# 05_-_I2C.net
KiCad netlist of a schematic drawn in Altium Designer
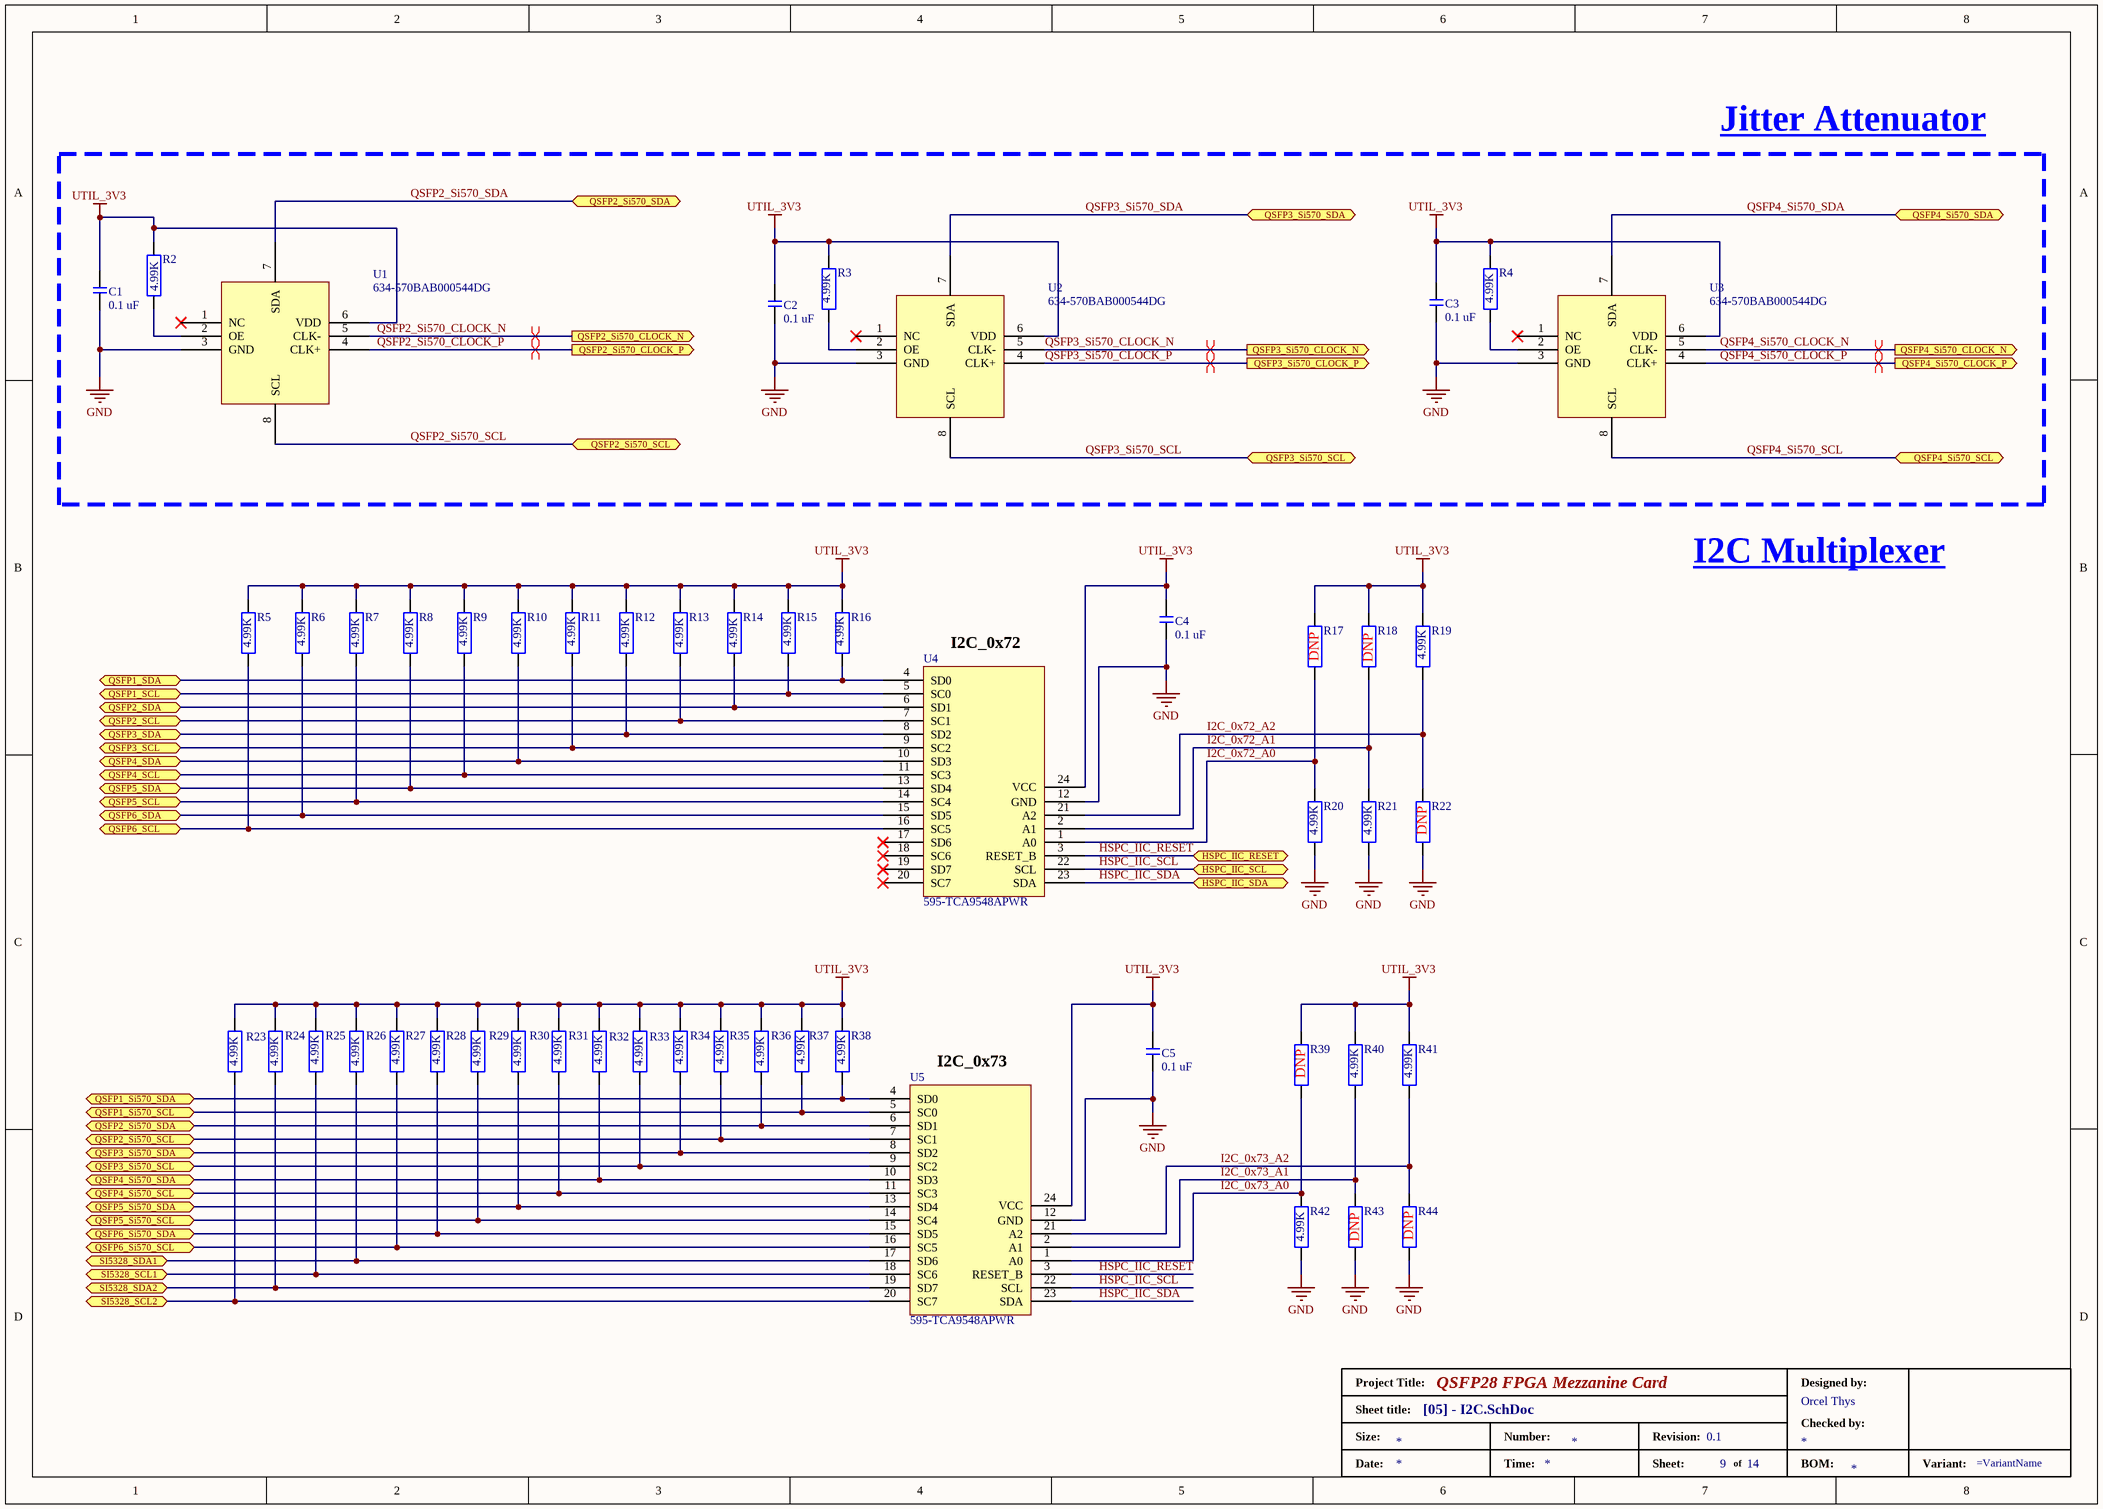
[diagram p0: [05] - I2C.SchDoc]

(export (version "E")
  (design (tool "Eeschema 10.0.6"))
  (components
    (comp (ref "C1")
      (value "0.1 uF")
      (footprint "C0402")
      (description "Cap 0402 0.1 uF 50 V ±10 % Tolerance X7R Surface Mount Multilayer Ceramic Capacitor")
      (fields
        (field (name "MANUFACTURER") "Taiyo Yuden")
        (field (name "MANUFACTURER PART NUMBER") "UMK105B7104KV-FR")
      )
      (libsource (lib "QSFP28_FMC_lib") (part "UMK105B7104KV-FR"))
    )
    (comp (ref "C2")
      (value "0.1 uF")
      (footprint "C0402")
      (description "Cap 0402 0.1 uF 50 V ±10 % Tolerance X7R Surface Mount Multilayer Ceramic Capacitor")
      (fields
        (field (name "MANUFACTURER") "Taiyo Yuden")
        (field (name "MANUFACTURER PART NUMBER") "UMK105B7104KV-FR")
      )
      (libsource (lib "QSFP28_FMC_lib") (part "UMK105B7104KV-FR"))
    )
    (comp (ref "C3")
      (value "0.1 uF")
      (footprint "C0402")
      (description "Cap 0402 0.1 uF 50 V ±10 % Tolerance X7R Surface Mount Multilayer Ceramic Capacitor")
      (fields
        (field (name "MANUFACTURER") "Taiyo Yuden")
        (field (name "MANUFACTURER PART NUMBER") "UMK105B7104KV-FR")
      )
      (libsource (lib "QSFP28_FMC_lib") (part "UMK105B7104KV-FR"))
    )
    (comp (ref "C4")
      (value "0.1 uF")
      (footprint "C0402")
      (description "Cap 0402 0.1 uF 50 V ±10 % Tolerance X7R Surface Mount Multilayer Ceramic Capacitor")
      (fields
        (field (name "MANUFACTURER") "Taiyo Yuden")
        (field (name "MANUFACTURER PART NUMBER") "UMK105B7104KV-FR")
      )
      (libsource (lib "QSFP28_FMC_lib") (part "UMK105B7104KV-FR"))
    )
    (comp (ref "C5")
      (value "0.1 uF")
      (footprint "C0402")
      (description "Cap 0402 0.1 uF 50 V ±10 % Tolerance X7R Surface Mount Multilayer Ceramic Capacitor")
      (fields
        (field (name "MANUFACTURER") "Taiyo Yuden")
        (field (name "MANUFACTURER PART NUMBER") "UMK105B7104KV-FR")
      )
      (libsource (lib "QSFP28_FMC_lib") (part "UMK105B7104KV-FR"))
    )
    (comp (ref "R2")
      (value "4.99K")
      (footprint "R0402")
      (description "RES SMD 4.99K OHM 1% 1/10W 0402")
      (fields
        (field (name "MANUFACTURER") "Panasonic")
        (field (name "MANUFACTURER PART NUMBER") "ERJ-2RKF4991X")
      )
      (libsource (lib "QSFP28_FMC_lib") (part "ERJ-2RKF4991X"))
    )
    (comp (ref "R3")
      (value "4.99K")
      (footprint "R0402")
      (description "RES SMD 4.99K OHM 1% 1/10W 0402")
      (fields
        (field (name "MANUFACTURER") "Panasonic")
        (field (name "MANUFACTURER PART NUMBER") "ERJ-2RKF4991X")
      )
      (libsource (lib "QSFP28_FMC_lib") (part "ERJ-2RKF4991X"))
    )
    (comp (ref "R4")
      (value "4.99K")
      (footprint "R0402")
      (description "RES SMD 4.99K OHM 1% 1/10W 0402")
      (fields
        (field (name "MANUFACTURER") "Panasonic")
        (field (name "MANUFACTURER PART NUMBER") "ERJ-2RKF4991X")
      )
      (libsource (lib "QSFP28_FMC_lib") (part "ERJ-2RKF4991X"))
    )
    (comp (ref "R5")
      (value "4.99K")
      (footprint "R0402")
      (description "RES SMD 4.99K OHM 1% 1/10W 0402")
      (fields
        (field (name "MANUFACTURER") "Panasonic")
        (field (name "MANUFACTURER PART NUMBER") "ERJ-2RKF4991X")
      )
      (libsource (lib "QSFP28_FMC_lib") (part "ERJ-2RKF4991X"))
    )
    (comp (ref "R6")
      (value "4.99K")
      (footprint "R0402")
      (description "RES SMD 4.99K OHM 1% 1/10W 0402")
      (fields
        (field (name "MANUFACTURER") "Panasonic")
        (field (name "MANUFACTURER PART NUMBER") "ERJ-2RKF4991X")
      )
      (libsource (lib "QSFP28_FMC_lib") (part "ERJ-2RKF4991X"))
    )
    (comp (ref "R7")
      (value "4.99K")
      (footprint "R0402")
      (description "RES SMD 4.99K OHM 1% 1/10W 0402")
      (fields
        (field (name "MANUFACTURER") "Panasonic")
        (field (name "MANUFACTURER PART NUMBER") "ERJ-2RKF4991X")
      )
      (libsource (lib "QSFP28_FMC_lib") (part "ERJ-2RKF4991X"))
    )
    (comp (ref "R8")
      (value "4.99K")
      (footprint "R0402")
      (description "RES SMD 4.99K OHM 1% 1/10W 0402")
      (fields
        (field (name "MANUFACTURER") "Panasonic")
        (field (name "MANUFACTURER PART NUMBER") "ERJ-2RKF4991X")
      )
      (libsource (lib "QSFP28_FMC_lib") (part "ERJ-2RKF4991X"))
    )
    (comp (ref "R9")
      (value "4.99K")
      (footprint "R0402")
      (description "RES SMD 4.99K OHM 1% 1/10W 0402")
      (fields
        (field (name "MANUFACTURER") "Panasonic")
        (field (name "MANUFACTURER PART NUMBER") "ERJ-2RKF4991X")
      )
      (libsource (lib "QSFP28_FMC_lib") (part "ERJ-2RKF4991X"))
    )
    (comp (ref "R10")
      (value "4.99K")
      (footprint "R0402")
      (description "RES SMD 4.99K OHM 1% 1/10W 0402")
      (fields
        (field (name "MANUFACTURER") "Panasonic")
        (field (name "MANUFACTURER PART NUMBER") "ERJ-2RKF4991X")
      )
      (libsource (lib "QSFP28_FMC_lib") (part "ERJ-2RKF4991X"))
    )
    (comp (ref "R11")
      (value "4.99K")
      (footprint "R0402")
      (description "RES SMD 4.99K OHM 1% 1/10W 0402")
      (fields
        (field (name "MANUFACTURER") "Panasonic")
        (field (name "MANUFACTURER PART NUMBER") "ERJ-2RKF4991X")
      )
      (libsource (lib "QSFP28_FMC_lib") (part "ERJ-2RKF4991X"))
    )
    (comp (ref "R12")
      (value "4.99K")
      (footprint "R0402")
      (description "RES SMD 4.99K OHM 1% 1/10W 0402")
      (fields
        (field (name "MANUFACTURER") "Panasonic")
        (field (name "MANUFACTURER PART NUMBER") "ERJ-2RKF4991X")
      )
      (libsource (lib "QSFP28_FMC_lib") (part "ERJ-2RKF4991X"))
    )
    (comp (ref "R13")
      (value "4.99K")
      (footprint "R0402")
      (description "RES SMD 4.99K OHM 1% 1/10W 0402")
      (fields
        (field (name "MANUFACTURER") "Panasonic")
        (field (name "MANUFACTURER PART NUMBER") "ERJ-2RKF4991X")
      )
      (libsource (lib "QSFP28_FMC_lib") (part "ERJ-2RKF4991X"))
    )
    (comp (ref "R14")
      (value "4.99K")
      (footprint "R0402")
      (description "RES SMD 4.99K OHM 1% 1/10W 0402")
      (fields
        (field (name "MANUFACTURER") "Panasonic")
        (field (name "MANUFACTURER PART NUMBER") "ERJ-2RKF4991X")
      )
      (libsource (lib "QSFP28_FMC_lib") (part "ERJ-2RKF4991X"))
    )
    (comp (ref "R15")
      (value "4.99K")
      (footprint "R0402")
      (description "RES SMD 4.99K OHM 1% 1/10W 0402")
      (fields
        (field (name "MANUFACTURER") "Panasonic")
        (field (name "MANUFACTURER PART NUMBER") "ERJ-2RKF4991X")
      )
      (libsource (lib "QSFP28_FMC_lib") (part "ERJ-2RKF4991X"))
    )
    (comp (ref "R16")
      (value "4.99K")
      (footprint "R0402")
      (description "RES SMD 4.99K OHM 1% 1/10W 0402")
      (fields
        (field (name "MANUFACTURER") "Panasonic")
        (field (name "MANUFACTURER PART NUMBER") "ERJ-2RKF4991X")
      )
      (libsource (lib "QSFP28_FMC_lib") (part "ERJ-2RKF4991X"))
    )
    (comp (ref "R17")
      (value "4.99K")
      (footprint "R0402")
      (description "RES SMD 4.99K OHM 1% 1/10W 0402")
      (fields
        (field (name "MANUFACTURER") "Panasonic")
        (field (name "MANUFACTURER PART NUMBER") "ERJ-2RKF4991X")
      )
      (libsource (lib "QSFP28_FMC_lib") (part "ERJ-2RKF4991X"))
    )
    (comp (ref "R18")
      (value "4.99K")
      (footprint "R0402")
      (description "RES SMD 4.99K OHM 1% 1/10W 0402")
      (fields
        (field (name "MANUFACTURER") "Panasonic")
        (field (name "MANUFACTURER PART NUMBER") "ERJ-2RKF4991X")
      )
      (libsource (lib "QSFP28_FMC_lib") (part "ERJ-2RKF4991X"))
    )
    (comp (ref "R19")
      (value "4.99K")
      (footprint "R0402")
      (description "RES SMD 4.99K OHM 1% 1/10W 0402")
      (fields
        (field (name "MANUFACTURER") "Panasonic")
        (field (name "MANUFACTURER PART NUMBER") "ERJ-2RKF4991X")
      )
      (libsource (lib "QSFP28_FMC_lib") (part "ERJ-2RKF4991X"))
    )
    (comp (ref "R20")
      (value "4.99K")
      (footprint "R0402")
      (description "RES SMD 4.99K OHM 1% 1/10W 0402")
      (fields
        (field (name "MANUFACTURER") "Panasonic")
        (field (name "MANUFACTURER PART NUMBER") "ERJ-2RKF4991X")
      )
      (libsource (lib "QSFP28_FMC_lib") (part "ERJ-2RKF4991X"))
    )
    (comp (ref "R21")
      (value "4.99K")
      (footprint "R0402")
      (description "RES SMD 4.99K OHM 1% 1/10W 0402")
      (fields
        (field (name "MANUFACTURER") "Panasonic")
        (field (name "MANUFACTURER PART NUMBER") "ERJ-2RKF4991X")
      )
      (libsource (lib "QSFP28_FMC_lib") (part "ERJ-2RKF4991X"))
    )
    (comp (ref "R22")
      (value "4.99K")
      (footprint "R0402")
      (description "RES SMD 4.99K OHM 1% 1/10W 0402")
      (fields
        (field (name "MANUFACTURER") "Panasonic")
        (field (name "MANUFACTURER PART NUMBER") "ERJ-2RKF4991X")
      )
      (libsource (lib "QSFP28_FMC_lib") (part "ERJ-2RKF4991X"))
    )
    (comp (ref "R23")
      (value "4.99K")
      (footprint "R0402")
      (description "RES SMD 4.99K OHM 1% 1/10W 0402")
      (fields
        (field (name "MANUFACTURER") "Panasonic")
        (field (name "MANUFACTURER PART NUMBER") "ERJ-2RKF4991X")
      )
      (libsource (lib "QSFP28_FMC_lib") (part "ERJ-2RKF4991X"))
    )
    (comp (ref "R24")
      (value "4.99K")
      (footprint "R0402")
      (description "RES SMD 4.99K OHM 1% 1/10W 0402")
      (fields
        (field (name "MANUFACTURER") "Panasonic")
        (field (name "MANUFACTURER PART NUMBER") "ERJ-2RKF4991X")
      )
      (libsource (lib "QSFP28_FMC_lib") (part "ERJ-2RKF4991X"))
    )
    (comp (ref "R25")
      (value "4.99K")
      (footprint "R0402")
      (description "RES SMD 4.99K OHM 1% 1/10W 0402")
      (fields
        (field (name "MANUFACTURER") "Panasonic")
        (field (name "MANUFACTURER PART NUMBER") "ERJ-2RKF4991X")
      )
      (libsource (lib "QSFP28_FMC_lib") (part "ERJ-2RKF4991X"))
    )
    (comp (ref "R26")
      (value "4.99K")
      (footprint "R0402")
      (description "RES SMD 4.99K OHM 1% 1/10W 0402")
      (fields
        (field (name "MANUFACTURER") "Panasonic")
        (field (name "MANUFACTURER PART NUMBER") "ERJ-2RKF4991X")
      )
      (libsource (lib "QSFP28_FMC_lib") (part "ERJ-2RKF4991X"))
    )
    (comp (ref "R27")
      (value "4.99K")
      (footprint "R0402")
      (description "RES SMD 4.99K OHM 1% 1/10W 0402")
      (fields
        (field (name "MANUFACTURER") "Panasonic")
        (field (name "MANUFACTURER PART NUMBER") "ERJ-2RKF4991X")
      )
      (libsource (lib "QSFP28_FMC_lib") (part "ERJ-2RKF4991X"))
    )
    (comp (ref "R28")
      (value "4.99K")
      (footprint "R0402")
      (description "RES SMD 4.99K OHM 1% 1/10W 0402")
      (fields
        (field (name "MANUFACTURER") "Panasonic")
        (field (name "MANUFACTURER PART NUMBER") "ERJ-2RKF4991X")
      )
      (libsource (lib "QSFP28_FMC_lib") (part "ERJ-2RKF4991X"))
    )
    (comp (ref "R29")
      (value "4.99K")
      (footprint "R0402")
      (description "RES SMD 4.99K OHM 1% 1/10W 0402")
      (fields
        (field (name "MANUFACTURER") "Panasonic")
        (field (name "MANUFACTURER PART NUMBER") "ERJ-2RKF4991X")
      )
      (libsource (lib "QSFP28_FMC_lib") (part "ERJ-2RKF4991X"))
    )
    (comp (ref "R30")
      (value "4.99K")
      (footprint "R0402")
      (description "RES SMD 4.99K OHM 1% 1/10W 0402")
      (fields
        (field (name "MANUFACTURER") "Panasonic")
        (field (name "MANUFACTURER PART NUMBER") "ERJ-2RKF4991X")
      )
      (libsource (lib "QSFP28_FMC_lib") (part "ERJ-2RKF4991X"))
    )
    (comp (ref "R31")
      (value "4.99K")
      (footprint "R0402")
      (description "RES SMD 4.99K OHM 1% 1/10W 0402")
      (fields
        (field (name "MANUFACTURER") "Panasonic")
        (field (name "MANUFACTURER PART NUMBER") "ERJ-2RKF4991X")
      )
      (libsource (lib "QSFP28_FMC_lib") (part "ERJ-2RKF4991X"))
    )
    (comp (ref "R32")
      (value "4.99K")
      (footprint "R0402")
      (description "RES SMD 4.99K OHM 1% 1/10W 0402")
      (fields
        (field (name "MANUFACTURER") "Panasonic")
        (field (name "MANUFACTURER PART NUMBER") "ERJ-2RKF4991X")
      )
      (libsource (lib "QSFP28_FMC_lib") (part "ERJ-2RKF4991X"))
    )
    (comp (ref "R33")
      (value "4.99K")
      (footprint "R0402")
      (description "RES SMD 4.99K OHM 1% 1/10W 0402")
      (fields
        (field (name "MANUFACTURER") "Panasonic")
        (field (name "MANUFACTURER PART NUMBER") "ERJ-2RKF4991X")
      )
      (libsource (lib "QSFP28_FMC_lib") (part "ERJ-2RKF4991X"))
    )
    (comp (ref "R34")
      (value "4.99K")
      (footprint "R0402")
      (description "RES SMD 4.99K OHM 1% 1/10W 0402")
      (fields
        (field (name "MANUFACTURER") "Panasonic")
        (field (name "MANUFACTURER PART NUMBER") "ERJ-2RKF4991X")
      )
      (libsource (lib "QSFP28_FMC_lib") (part "ERJ-2RKF4991X"))
    )
    (comp (ref "R35")
      (value "4.99K")
      (footprint "R0402")
      (description "RES SMD 4.99K OHM 1% 1/10W 0402")
      (fields
        (field (name "MANUFACTURER") "Panasonic")
        (field (name "MANUFACTURER PART NUMBER") "ERJ-2RKF4991X")
      )
      (libsource (lib "QSFP28_FMC_lib") (part "ERJ-2RKF4991X"))
    )
    (comp (ref "R36")
      (value "4.99K")
      (footprint "R0402")
      (description "RES SMD 4.99K OHM 1% 1/10W 0402")
      (fields
        (field (name "MANUFACTURER") "Panasonic")
        (field (name "MANUFACTURER PART NUMBER") "ERJ-2RKF4991X")
      )
      (libsource (lib "QSFP28_FMC_lib") (part "ERJ-2RKF4991X"))
    )
    (comp (ref "R37")
      (value "4.99K")
      (footprint "R0402")
      (description "RES SMD 4.99K OHM 1% 1/10W 0402")
      (fields
        (field (name "MANUFACTURER") "Panasonic")
        (field (name "MANUFACTURER PART NUMBER") "ERJ-2RKF4991X")
      )
      (libsource (lib "QSFP28_FMC_lib") (part "ERJ-2RKF4991X"))
    )
    (comp (ref "R38")
      (value "4.99K")
      (footprint "R0402")
      (description "RES SMD 4.99K OHM 1% 1/10W 0402")
      (fields
        (field (name "MANUFACTURER") "Panasonic")
        (field (name "MANUFACTURER PART NUMBER") "ERJ-2RKF4991X")
      )
      (libsource (lib "QSFP28_FMC_lib") (part "ERJ-2RKF4991X"))
    )
    (comp (ref "R39")
      (value "4.99K")
      (footprint "R0402")
      (description "RES SMD 4.99K OHM 1% 1/10W 0402")
      (fields
        (field (name "MANUFACTURER") "Panasonic")
        (field (name "MANUFACTURER PART NUMBER") "ERJ-2RKF4991X")
      )
      (libsource (lib "QSFP28_FMC_lib") (part "ERJ-2RKF4991X"))
    )
    (comp (ref "R40")
      (value "4.99K")
      (footprint "R0402")
      (description "RES SMD 4.99K OHM 1% 1/10W 0402")
      (fields
        (field (name "MANUFACTURER") "Panasonic")
        (field (name "MANUFACTURER PART NUMBER") "ERJ-2RKF4991X")
      )
      (libsource (lib "QSFP28_FMC_lib") (part "ERJ-2RKF4991X"))
    )
    (comp (ref "R41")
      (value "4.99K")
      (footprint "R0402")
      (description "RES SMD 4.99K OHM 1% 1/10W 0402")
      (fields
        (field (name "MANUFACTURER") "Panasonic")
        (field (name "MANUFACTURER PART NUMBER") "ERJ-2RKF4991X")
      )
      (libsource (lib "QSFP28_FMC_lib") (part "ERJ-2RKF4991X"))
    )
    (comp (ref "R42")
      (value "4.99K")
      (footprint "R0402")
      (description "RES SMD 4.99K OHM 1% 1/10W 0402")
      (fields
        (field (name "MANUFACTURER") "Panasonic")
        (field (name "MANUFACTURER PART NUMBER") "ERJ-2RKF4991X")
      )
      (libsource (lib "QSFP28_FMC_lib") (part "ERJ-2RKF4991X"))
    )
    (comp (ref "R43")
      (value "4.99K")
      (footprint "R0402")
      (description "RES SMD 4.99K OHM 1% 1/10W 0402")
      (fields
        (field (name "MANUFACTURER") "Panasonic")
        (field (name "MANUFACTURER PART NUMBER") "ERJ-2RKF4991X")
      )
      (libsource (lib "QSFP28_FMC_lib") (part "ERJ-2RKF4991X"))
    )
    (comp (ref "R44")
      (value "4.99K")
      (footprint "R0402")
      (description "RES SMD 4.99K OHM 1% 1/10W 0402")
      (fields
        (field (name "MANUFACTURER") "Panasonic")
        (field (name "MANUFACTURER PART NUMBER") "ERJ-2RKF4991X")
      )
      (libsource (lib "QSFP28_FMC_lib") (part "ERJ-2RKF4991X"))
    )
    (comp (ref "U1")
      (value "Si570")
      (footprint "Si570")
      (description "10 MHZ TO 810 MHZ I2C PROG 0x5D, 156.25MHz DEFAULT")
      (fields
        (field (name "MANUFACTURER") "Skyworks Solutions")
        (field (name "MANUFACTURER PART NUMBER") "570BAB000544DG")
        (field (name "SUPPLIER PART NUMBER 1") "634-570BAB000544DG")
      )
      (libsource (lib "QSFP28_FMC_lib") (part "570BAB000544DG"))
    )
    (comp (ref "U2")
      (value "Si570")
      (footprint "Si570")
      (description "10 MHZ TO 810 MHZ I2C PROG 0x5D, 156.25MHz DEFAULT")
      (fields
        (field (name "MANUFACTURER") "Skyworks Solutions")
        (field (name "MANUFACTURER PART NUMBER") "570BAB000544DG")
        (field (name "SUPPLIER PART NUMBER 1") "634-570BAB000544DG")
      )
      (libsource (lib "QSFP28_FMC_lib") (part "570BAB000544DG"))
    )
    (comp (ref "U3")
      (value "Si570")
      (footprint "Si570")
      (description "10 MHZ TO 810 MHZ I2C PROG 0x5D, 156.25MHz DEFAULT")
      (fields
        (field (name "MANUFACTURER") "Skyworks Solutions")
        (field (name "MANUFACTURER PART NUMBER") "570BAB000544DG")
        (field (name "SUPPLIER PART NUMBER 1") "634-570BAB000544DG")
      )
      (libsource (lib "QSFP28_FMC_lib") (part "570BAB000544DG"))
    )
    (comp (ref "U4")
      (value "8-Channels I2C switch")
      (footprint "SOP_65P640X120-24N")
      (description "IC I2C SW 8CH W/RESET 24TSSOP")
      (fields
        (field (name "MANUFACTURER") "Texas Instruments")
        (field (name "MANUFACTURER PART NUMBER") "TCA9548APWR")
        (field (name "SUPPLIER PART NUMBER 1") "595-TCA9548APWR")
      )
      (libsource (lib "FmcLib") (part "TCA9548APWR"))
    )
    (comp (ref "U5")
      (value "8-Channels I2C switch")
      (footprint "SOP_65P640X120-24N")
      (description "IC I2C SW 8CH W/RESET 24TSSOP")
      (fields
        (field (name "MANUFACTURER") "Texas Instruments")
        (field (name "MANUFACTURER PART NUMBER") "TCA9548APWR")
        (field (name "SUPPLIER PART NUMBER 1") "595-TCA9548APWR")
      )
      (libsource (lib "FmcLib") (part "TCA9548APWR"))
    )
  )
  (nets
    (net (code "1") (name "/HSPC_IIC_RESET") (class "Default")
      (node (ref "U4") (pin "3") (pinfunction "RESET_B_3") (pintype "passive"))
      (node (ref "U5") (pin "3") (pinfunction "RESET_B_3") (pintype "passive"))
    )
    (net (code "2") (name "/HSPC_IIC_SCL") (class "Default")
      (node (ref "U4") (pin "22") (pinfunction "SCL_22") (pintype "passive"))
      (node (ref "U5") (pin "22") (pinfunction "SCL_22") (pintype "passive"))
    )
    (net (code "3") (name "/HSPC_IIC_SDA") (class "Default")
      (node (ref "U4") (pin "23") (pinfunction "SDA_23") (pintype "passive"))
      (node (ref "U5") (pin "23") (pinfunction "SDA_23") (pintype "passive"))
    )
    (net (code "4") (name "/I2C_0x72_A0") (class "Default")
      (node (ref "R17") (pin "1") (pintype "passive"))
      (node (ref "R20") (pin "2") (pintype "passive"))
      (node (ref "U4") (pin "1") (pinfunction "A0_1") (pintype "passive"))
    )
    (net (code "5") (name "/I2C_0x72_A1") (class "Default")
      (node (ref "R18") (pin "1") (pintype "passive"))
      (node (ref "R21") (pin "2") (pintype "passive"))
      (node (ref "U4") (pin "2") (pinfunction "A1_2") (pintype "passive"))
    )
    (net (code "6") (name "/I2C_0x72_A2") (class "Default")
      (node (ref "R19") (pin "1") (pintype "passive"))
      (node (ref "R22") (pin "2") (pintype "passive"))
      (node (ref "U4") (pin "21") (pinfunction "A2_21") (pintype "passive"))
    )
    (net (code "7") (name "/I2C_0x73_A0") (class "Default")
      (node (ref "R39") (pin "1") (pintype "passive"))
      (node (ref "R42") (pin "2") (pintype "passive"))
      (node (ref "U5") (pin "1") (pinfunction "A0_1") (pintype "passive"))
    )
    (net (code "8") (name "/I2C_0x73_A1") (class "Default")
      (node (ref "R40") (pin "1") (pintype "passive"))
      (node (ref "R43") (pin "2") (pintype "passive"))
      (node (ref "U5") (pin "2") (pinfunction "A1_2") (pintype "passive"))
    )
    (net (code "9") (name "/I2C_0x73_A2") (class "Default")
      (node (ref "R41") (pin "1") (pintype "passive"))
      (node (ref "R44") (pin "2") (pintype "passive"))
      (node (ref "U5") (pin "21") (pinfunction "A2_21") (pintype "passive"))
    )
    (net (code "10") (name "/QSFP1_SCL") (class "Default")
      (node (ref "R15") (pin "1") (pintype "passive"))
      (node (ref "U4") (pin "5") (pinfunction "SC0_5") (pintype "passive"))
    )
    (net (code "11") (name "/QSFP1_SDA") (class "Default")
      (node (ref "R16") (pin "1") (pintype "passive"))
      (node (ref "U4") (pin "4") (pinfunction "SD0_4") (pintype "passive"))
    )
    (net (code "12") (name "/QSFP1_Si570_SCL") (class "Default")
      (node (ref "R37") (pin "1") (pintype "passive"))
      (node (ref "U5") (pin "5") (pinfunction "SC0_5") (pintype "passive"))
    )
    (net (code "13") (name "/QSFP1_Si570_SDA") (class "Default")
      (node (ref "R38") (pin "1") (pintype "passive"))
      (node (ref "U5") (pin "4") (pinfunction "SD0_4") (pintype "passive"))
    )
    (net (code "14") (name "/QSFP2_SCL") (class "Default")
      (node (ref "R13") (pin "1") (pintype "passive"))
      (node (ref "U4") (pin "7") (pinfunction "SC1_7") (pintype "passive"))
    )
    (net (code "15") (name "/QSFP2_SDA") (class "Default")
      (node (ref "R14") (pin "1") (pintype "passive"))
      (node (ref "U4") (pin "6") (pinfunction "SD1_6") (pintype "passive"))
    )
    (net (code "16") (name "/QSFP2_Si570_CLOCK_N") (class "Default")
      (node (ref "U1") (pin "5") (pinfunction "CLK-_5") (pintype "passive"))
    )
    (net (code "17") (name "/QSFP2_Si570_CLOCK_P") (class "Default")
      (node (ref "U1") (pin "4") (pinfunction "CLK+_4") (pintype "passive"))
    )
    (net (code "18") (name "/QSFP2_Si570_SCL") (class "Default")
      (node (ref "R35") (pin "1") (pintype "passive"))
      (node (ref "U1") (pin "8") (pinfunction "SCL_8") (pintype "passive"))
      (node (ref "U5") (pin "7") (pinfunction "SC1_7") (pintype "passive"))
    )
    (net (code "19") (name "/QSFP2_Si570_SDA") (class "Default")
      (node (ref "R36") (pin "1") (pintype "passive"))
      (node (ref "U1") (pin "7") (pinfunction "SDA_7") (pintype "passive"))
      (node (ref "U5") (pin "6") (pinfunction "SD1_6") (pintype "passive"))
    )
    (net (code "20") (name "/QSFP3_SCL") (class "Default")
      (node (ref "R11") (pin "1") (pintype "passive"))
      (node (ref "U4") (pin "9") (pinfunction "SC2_9") (pintype "passive"))
    )
    (net (code "21") (name "/QSFP3_SDA") (class "Default")
      (node (ref "R12") (pin "1") (pintype "passive"))
      (node (ref "U4") (pin "8") (pinfunction "SD2_8") (pintype "passive"))
    )
    (net (code "22") (name "/QSFP3_Si570_CLOCK_N") (class "Default")
      (node (ref "U2") (pin "5") (pinfunction "CLK-_5") (pintype "passive"))
    )
    (net (code "23") (name "/QSFP3_Si570_CLOCK_P") (class "Default")
      (node (ref "U2") (pin "4") (pinfunction "CLK+_4") (pintype "passive"))
    )
    (net (code "24") (name "/QSFP3_Si570_SCL") (class "Default")
      (node (ref "R33") (pin "1") (pintype "passive"))
      (node (ref "U2") (pin "8") (pinfunction "SCL_8") (pintype "passive"))
      (node (ref "U5") (pin "9") (pinfunction "SC2_9") (pintype "passive"))
    )
    (net (code "25") (name "/QSFP3_Si570_SDA") (class "Default")
      (node (ref "R34") (pin "1") (pintype "passive"))
      (node (ref "U2") (pin "7") (pinfunction "SDA_7") (pintype "passive"))
      (node (ref "U5") (pin "8") (pinfunction "SD2_8") (pintype "passive"))
    )
    (net (code "26") (name "/QSFP4_SCL") (class "Default")
      (node (ref "R9") (pin "1") (pintype "passive"))
      (node (ref "U4") (pin "11") (pinfunction "SC3_11") (pintype "passive"))
    )
    (net (code "27") (name "/QSFP4_SDA") (class "Default")
      (node (ref "R10") (pin "1") (pintype "passive"))
      (node (ref "U4") (pin "10") (pinfunction "SD3_10") (pintype "passive"))
    )
    (net (code "28") (name "/QSFP4_Si570_CLOCK_N") (class "Default")
      (node (ref "U3") (pin "5") (pinfunction "CLK-_5") (pintype "passive"))
    )
    (net (code "29") (name "/QSFP4_Si570_CLOCK_P") (class "Default")
      (node (ref "U3") (pin "4") (pinfunction "CLK+_4") (pintype "passive"))
    )
    (net (code "30") (name "/QSFP4_Si570_SCL") (class "Default")
      (node (ref "R31") (pin "1") (pintype "passive"))
      (node (ref "U3") (pin "8") (pinfunction "SCL_8") (pintype "passive"))
      (node (ref "U5") (pin "11") (pinfunction "SC3_11") (pintype "passive"))
    )
    (net (code "31") (name "/QSFP4_Si570_SDA") (class "Default")
      (node (ref "R32") (pin "1") (pintype "passive"))
      (node (ref "U3") (pin "7") (pinfunction "SDA_7") (pintype "passive"))
      (node (ref "U5") (pin "10") (pinfunction "SD3_10") (pintype "passive"))
    )
    (net (code "32") (name "/QSFP5_SCL") (class "Default")
      (node (ref "R7") (pin "1") (pintype "passive"))
      (node (ref "U4") (pin "14") (pinfunction "SC4_14") (pintype "passive"))
    )
    (net (code "33") (name "/QSFP5_SDA") (class "Default")
      (node (ref "R8") (pin "1") (pintype "passive"))
      (node (ref "U4") (pin "13") (pinfunction "SD4_13") (pintype "passive"))
    )
    (net (code "34") (name "/QSFP5_Si570_SCL") (class "Default")
      (node (ref "R29") (pin "1") (pintype "passive"))
      (node (ref "U5") (pin "14") (pinfunction "SC4_14") (pintype "passive"))
    )
    (net (code "35") (name "/QSFP5_Si570_SDA") (class "Default")
      (node (ref "R30") (pin "1") (pintype "passive"))
      (node (ref "U5") (pin "13") (pinfunction "SD4_13") (pintype "passive"))
    )
    (net (code "36") (name "/QSFP6_SCL") (class "Default")
      (node (ref "R5") (pin "1") (pintype "passive"))
      (node (ref "U4") (pin "16") (pinfunction "SC5_16") (pintype "passive"))
    )
    (net (code "37") (name "/QSFP6_SDA") (class "Default")
      (node (ref "R6") (pin "1") (pintype "passive"))
      (node (ref "U4") (pin "15") (pinfunction "SD5_15") (pintype "passive"))
    )
    (net (code "38") (name "/QSFP6_Si570_SCL") (class "Default")
      (node (ref "R27") (pin "1") (pintype "passive"))
      (node (ref "U5") (pin "16") (pinfunction "SC5_16") (pintype "passive"))
    )
    (net (code "39") (name "/QSFP6_Si570_SDA") (class "Default")
      (node (ref "R28") (pin "1") (pintype "passive"))
      (node (ref "U5") (pin "15") (pinfunction "SD5_15") (pintype "passive"))
    )
    (net (code "40") (name "/SI5328_SCL1") (class "Default")
      (node (ref "R25") (pin "1") (pintype "passive"))
      (node (ref "U5") (pin "18") (pinfunction "SC6_18") (pintype "passive"))
    )
    (net (code "41") (name "/SI5328_SCL2") (class "Default")
      (node (ref "R23") (pin "1") (pintype "passive"))
      (node (ref "U5") (pin "20") (pinfunction "SC7_20") (pintype "passive"))
    )
    (net (code "42") (name "/SI5328_SDA1") (class "Default")
      (node (ref "R26") (pin "1") (pintype "passive"))
      (node (ref "U5") (pin "17") (pinfunction "SD6_17") (pintype "passive"))
    )
    (net (code "43") (name "/SI5328_SDA2") (class "Default")
      (node (ref "R24") (pin "1") (pintype "passive"))
      (node (ref "U5") (pin "19") (pinfunction "SD7_19") (pintype "passive"))
    )
    (net (code "44") (name "GND") (class "Default")
      (node (ref "C1") (pin "2") (pinfunction "2_2") (pintype "passive"))
      (node (ref "C2") (pin "2") (pinfunction "2_2") (pintype "passive"))
      (node (ref "C3") (pin "2") (pinfunction "2_2") (pintype "passive"))
      (node (ref "C4") (pin "1") (pinfunction "1_1") (pintype "passive"))
      (node (ref "C5") (pin "1") (pinfunction "1_1") (pintype "passive"))
      (node (ref "R20") (pin "1") (pintype "passive"))
      (node (ref "R21") (pin "1") (pintype "passive"))
      (node (ref "R22") (pin "1") (pintype "passive"))
      (node (ref "R42") (pin "1") (pintype "passive"))
      (node (ref "R43") (pin "1") (pintype "passive"))
      (node (ref "R44") (pin "1") (pintype "passive"))
      (node (ref "U1") (pin "3") (pinfunction "GND_3") (pintype "passive"))
      (node (ref "U2") (pin "3") (pinfunction "GND_3") (pintype "passive"))
      (node (ref "U3") (pin "3") (pinfunction "GND_3") (pintype "passive"))
      (node (ref "U4") (pin "12") (pinfunction "GND_12") (pintype "passive"))
      (node (ref "U5") (pin "12") (pinfunction "GND_12") (pintype "passive"))
    )
    (net (code "45") (name "Net-(U1-OE)") (class "Default")
      (node (ref "R2") (pin "1") (pintype "passive"))
      (node (ref "U1") (pin "2") (pinfunction "OE_2") (pintype "passive"))
    )
    (net (code "46") (name "Net-(U2-OE)") (class "Default")
      (node (ref "R3") (pin "1") (pintype "passive"))
      (node (ref "U2") (pin "2") (pinfunction "OE_2") (pintype "passive"))
    )
    (net (code "47") (name "Net-(U3-OE)") (class "Default")
      (node (ref "R4") (pin "1") (pintype "passive"))
      (node (ref "U3") (pin "2") (pinfunction "OE_2") (pintype "passive"))
    )
    (net (code "48") (name "UTIL_3V3") (class "Default")
      (node (ref "C1") (pin "1") (pinfunction "1_1") (pintype "passive"))
      (node (ref "C2") (pin "1") (pinfunction "1_1") (pintype "passive"))
      (node (ref "C3") (pin "1") (pinfunction "1_1") (pintype "passive"))
      (node (ref "C4") (pin "2") (pinfunction "2_2") (pintype "passive"))
      (node (ref "C5") (pin "2") (pinfunction "2_2") (pintype "passive"))
      (node (ref "R10") (pin "2") (pintype "passive"))
      (node (ref "R11") (pin "2") (pintype "passive"))
      (node (ref "R12") (pin "2") (pintype "passive"))
      (node (ref "R13") (pin "2") (pintype "passive"))
      (node (ref "R14") (pin "2") (pintype "passive"))
      (node (ref "R15") (pin "2") (pintype "passive"))
      (node (ref "R16") (pin "2") (pintype "passive"))
      (node (ref "R17") (pin "2") (pintype "passive"))
      (node (ref "R18") (pin "2") (pintype "passive"))
      (node (ref "R19") (pin "2") (pintype "passive"))
      (node (ref "R2") (pin "2") (pintype "passive"))
      (node (ref "R23") (pin "2") (pintype "passive"))
      (node (ref "R24") (pin "2") (pintype "passive"))
      (node (ref "R25") (pin "2") (pintype "passive"))
      (node (ref "R26") (pin "2") (pintype "passive"))
      (node (ref "R27") (pin "2") (pintype "passive"))
      (node (ref "R28") (pin "2") (pintype "passive"))
      (node (ref "R29") (pin "2") (pintype "passive"))
      (node (ref "R3") (pin "2") (pintype "passive"))
      (node (ref "R30") (pin "2") (pintype "passive"))
      (node (ref "R31") (pin "2") (pintype "passive"))
      (node (ref "R32") (pin "2") (pintype "passive"))
      (node (ref "R33") (pin "2") (pintype "passive"))
      (node (ref "R34") (pin "2") (pintype "passive"))
      (node (ref "R35") (pin "2") (pintype "passive"))
      (node (ref "R36") (pin "2") (pintype "passive"))
      (node (ref "R37") (pin "2") (pintype "passive"))
      (node (ref "R38") (pin "2") (pintype "passive"))
      (node (ref "R39") (pin "2") (pintype "passive"))
      (node (ref "R4") (pin "2") (pintype "passive"))
      (node (ref "R40") (pin "2") (pintype "passive"))
      (node (ref "R41") (pin "2") (pintype "passive"))
      (node (ref "R5") (pin "2") (pintype "passive"))
      (node (ref "R6") (pin "2") (pintype "passive"))
      (node (ref "R7") (pin "2") (pintype "passive"))
      (node (ref "R8") (pin "2") (pintype "passive"))
      (node (ref "R9") (pin "2") (pintype "passive"))
      (node (ref "U1") (pin "6") (pinfunction "VDD_6") (pintype "passive"))
      (node (ref "U2") (pin "6") (pinfunction "VDD_6") (pintype "passive"))
      (node (ref "U3") (pin "6") (pinfunction "VDD_6") (pintype "passive"))
      (node (ref "U4") (pin "24") (pinfunction "VCC_24") (pintype "passive"))
      (node (ref "U5") (pin "24") (pinfunction "VCC_24") (pintype "passive"))
    )
    (net (code "49") (name "unconnected-(U1-NC-Pad1)") (class "Default")
      (node (ref "U1") (pin "1") (pinfunction "NC_1") (pintype "passive+no_connect"))
    )
    (net (code "50") (name "unconnected-(U2-NC-Pad1)") (class "Default")
      (node (ref "U2") (pin "1") (pinfunction "NC_1") (pintype "passive+no_connect"))
    )
    (net (code "51") (name "unconnected-(U3-NC-Pad1)") (class "Default")
      (node (ref "U3") (pin "1") (pinfunction "NC_1") (pintype "passive+no_connect"))
    )
    (net (code "52") (name "unconnected-(U4-SC6-Pad18)") (class "Default")
      (node (ref "U4") (pin "18") (pinfunction "SC6_18") (pintype "passive+no_connect"))
    )
    (net (code "53") (name "unconnected-(U4-SC7-Pad20)") (class "Default")
      (node (ref "U4") (pin "20") (pinfunction "SC7_20") (pintype "passive+no_connect"))
    )
    (net (code "54") (name "unconnected-(U4-SD6-Pad17)") (class "Default")
      (node (ref "U4") (pin "17") (pinfunction "SD6_17") (pintype "passive+no_connect"))
    )
    (net (code "55") (name "unconnected-(U4-SD7-Pad19)") (class "Default")
      (node (ref "U4") (pin "19") (pinfunction "SD7_19") (pintype "passive+no_connect"))
    )
  )
)
